# rfm26w_breakout_board.net
KiCad netlist of a schematic drawn in EAGLE
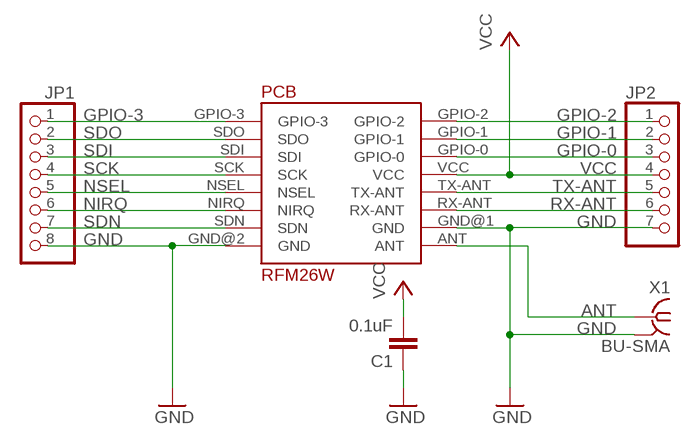
[diagram p0: schematic, sheet 1]

(export (version "E")
  (design (tool "Eeschema 10.0.6"))
  (components
    (comp (ref "C1")
      (value "0.1uF")
      (footprint "eagle-import:C0805K")
      (libsource (lib "eagle-import") (part "C-EUC0805K"))
    )
    (comp (ref "JP1")
      (value "PINHD-1X8")
      (footprint "eagle-import:1X08")
      (libsource (lib "eagle-import") (part "PINHD-1X8"))
    )
    (comp (ref "JP2")
      (value "PINHD-1X7")
      (footprint "eagle-import:1X07")
      (libsource (lib "eagle-import") (part "PINHD-1X7"))
    )
    (comp (ref "PCB")
      (value "RFM26W")
      (footprint "eagle-import:RFM26W")
      (libsource (lib "eagle-import") (part "RFM26W"))
    )
    (comp (ref "X1")
      (value "BU-SMA")
      (footprint "eagle-import:BU-SMA-V")
      (libsource (lib "eagle-import") (part "BU-SMA-V"))
    )
  )
  (nets
    (net (code "1") (name "/ANT") (class "Default")
      (node (ref "PCB") (pin "ANT") (pinfunction "ANT_ANT") (pintype "bidirectional"))
      (node (ref "X1") (pin "1") (pinfunction "1_1") (pintype "passive"))
    )
    (net (code "2") (name "/GPIO-0") (class "Default")
      (node (ref "JP2") (pin "3") (pinfunction "3_3") (pintype "passive"))
      (node (ref "PCB") (pin "GPIO-0") (pinfunction "GPIO-0_GPIO-0") (pintype "bidirectional"))
    )
    (net (code "3") (name "/GPIO-1") (class "Default")
      (node (ref "JP2") (pin "2") (pinfunction "2_2") (pintype "passive"))
      (node (ref "PCB") (pin "GPIO-1") (pinfunction "GPIO-1_GPIO-1") (pintype "bidirectional"))
    )
    (net (code "4") (name "/GPIO-2") (class "Default")
      (node (ref "JP2") (pin "1") (pinfunction "1_1") (pintype "passive"))
      (node (ref "PCB") (pin "GPIO-2") (pinfunction "GPIO-2_GPIO-2") (pintype "bidirectional"))
    )
    (net (code "5") (name "/GPIO-3") (class "Default")
      (node (ref "JP1") (pin "1") (pinfunction "1_1") (pintype "passive"))
      (node (ref "PCB") (pin "GPIO-3") (pinfunction "GPIO-3_GPIO-3") (pintype "bidirectional"))
    )
    (net (code "6") (name "/NIRQ") (class "Default")
      (node (ref "JP1") (pin "6") (pinfunction "6_6") (pintype "passive"))
      (node (ref "PCB") (pin "NIRQ") (pinfunction "NIRQ_NIRQ") (pintype "bidirectional"))
    )
    (net (code "7") (name "/NSEL") (class "Default")
      (node (ref "JP1") (pin "5") (pinfunction "5_5") (pintype "passive"))
      (node (ref "PCB") (pin "NSEL") (pinfunction "NSEL_NSEL") (pintype "bidirectional"))
    )
    (net (code "8") (name "/RX-ANT") (class "Default")
      (node (ref "JP2") (pin "6") (pinfunction "6_6") (pintype "passive"))
      (node (ref "PCB") (pin "RX-ANT") (pinfunction "RX-ANT_RX-ANT") (pintype "bidirectional"))
    )
    (net (code "9") (name "/SCK") (class "Default")
      (node (ref "JP1") (pin "4") (pinfunction "4_4") (pintype "passive"))
      (node (ref "PCB") (pin "SCK") (pinfunction "SCK_SCK") (pintype "bidirectional"))
    )
    (net (code "10") (name "/SDI") (class "Default")
      (node (ref "JP1") (pin "3") (pinfunction "3_3") (pintype "passive"))
      (node (ref "PCB") (pin "SDI") (pinfunction "SDI_SDI") (pintype "bidirectional"))
    )
    (net (code "11") (name "/SDN") (class "Default")
      (node (ref "JP1") (pin "7") (pinfunction "7_7") (pintype "passive"))
      (node (ref "PCB") (pin "SDN") (pinfunction "SDN_SDN") (pintype "bidirectional"))
    )
    (net (code "12") (name "/SDO") (class "Default")
      (node (ref "JP1") (pin "2") (pinfunction "2_2") (pintype "passive"))
      (node (ref "PCB") (pin "SDO") (pinfunction "SDO_SDO") (pintype "bidirectional"))
    )
    (net (code "13") (name "/TX-ANT") (class "Default")
      (node (ref "JP2") (pin "5") (pinfunction "5_5") (pintype "passive"))
      (node (ref "PCB") (pin "TX-ANT") (pinfunction "TX-ANT_TX-ANT") (pintype "bidirectional"))
    )
    (net (code "14") (name "GND") (class "Default")
      (node (ref "C1") (pin "1") (pinfunction "1_1") (pintype "passive"))
      (node (ref "JP1") (pin "8") (pinfunction "8_8") (pintype "passive"))
      (node (ref "JP2") (pin "7") (pinfunction "7_7") (pintype "passive"))
      (node (ref "PCB") (pin "GND@1") (pinfunction "GND_GND@1") (pintype "power_in"))
      (node (ref "PCB") (pin "GND@2") (pinfunction "GND_GND@2") (pintype "power_in"))
      (node (ref "X1") (pin "2") (pinfunction "2_2") (pintype "passive"))
      (node (ref "X1") (pin "3") (pinfunction "2_3") (pintype "passive"))
      (node (ref "X1") (pin "4") (pinfunction "2_4") (pintype "passive"))
      (node (ref "X1") (pin "5") (pinfunction "2_5") (pintype "passive"))
    )
    (net (code "15") (name "VCC") (class "Default")
      (node (ref "C1") (pin "2") (pinfunction "2_2") (pintype "passive"))
      (node (ref "JP2") (pin "4") (pinfunction "4_4") (pintype "passive"))
      (node (ref "PCB") (pin "VCC") (pinfunction "VCC_VCC") (pintype "power_in"))
    )
  )
)
